# Rangefinders.net
KiCad netlist of a schematic drawn in Altium Designer
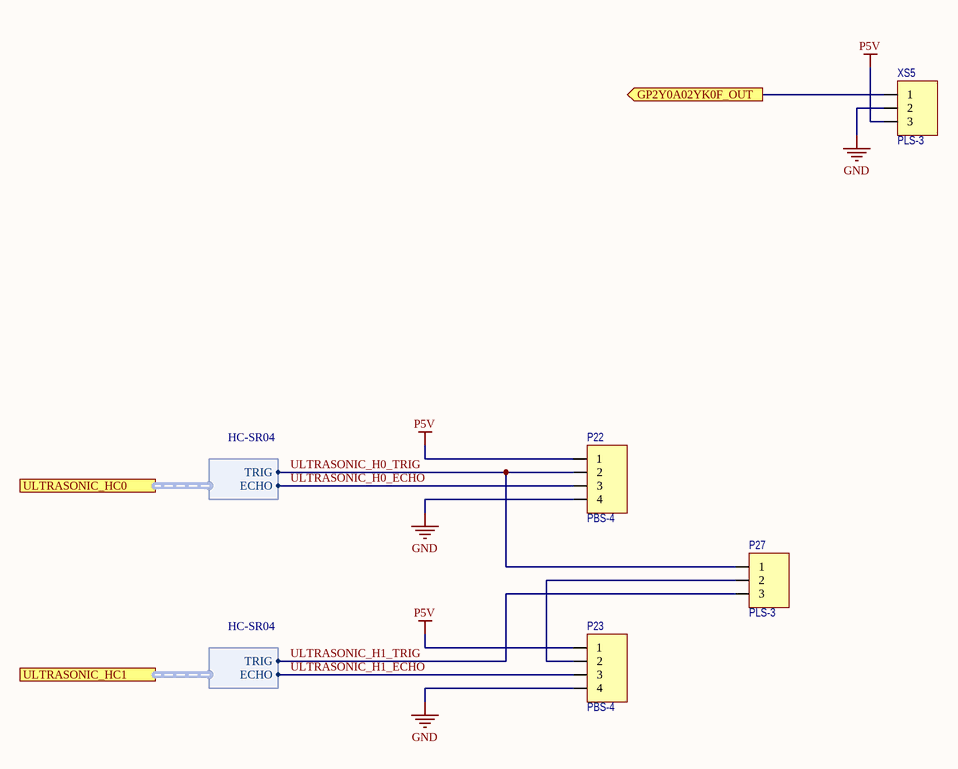
[diagram p0: Rangefinders.SchDoc]

(export (version "E")
  (design (tool "Eeschema 10.0.6"))
  (components
    (comp (ref "P22") (value "PBS-4") (footprint "PBS-4") (libsource (lib "my_AP_lib_sch") (part "PBS-4")))
    (comp (ref "P23") (value "PBS-4") (footprint "PBS-4") (libsource (lib "my_AP_lib_sch") (part "PBS-4")))
    (comp (ref "P27") (value "PLS-3") (footprint "PLS-3") (libsource (lib "my_AP_lib_sch") (part "PLS-3")))
    (comp (ref "XS5") (value "PLS-3") (footprint "PBS2-3") (libsource (lib "my_AP_lib_sch") (part "PBS2-3")))
  )
  (nets
    (net (code "2") (name "/GP2Y0A02YK0F_OUT") (class "Default")
      (node (ref "XS5") (pin "1") (pinfunction "1_1") (pintype "passive"))
    )
    (net (code "3") (name "/ULTRASONIC_H0_ECHO") (class "Default")
      (node (ref "P22") (pin "3") (pinfunction "3_3") (pintype "passive"))
    )
    (net (code "4") (name "/ULTRASONIC_H0_TRIG") (class "Default")
      (node (ref "P22") (pin "2") (pinfunction "2_2") (pintype "passive"))
      (node (ref "P27") (pin "1") (pinfunction "1_1") (pintype "passive"))
    )
    (net (code "5") (name "/ULTRASONIC_H1_ECHO") (class "Default")
      (node (ref "P23") (pin "3") (pinfunction "3_3") (pintype "passive"))
    )
    (net (code "6") (name "/ULTRASONIC_H1_TRIG") (class "Default")
      (node (ref "P27") (pin "3") (pinfunction "3_3") (pintype "passive"))
    )
    (net (code "8") (name "GND") (class "Default")
      (node (ref "P22") (pin "4") (pinfunction "4_4") (pintype "passive"))
      (node (ref "P23") (pin "4") (pinfunction "4_4") (pintype "passive"))
      (node (ref "XS5") (pin "2") (pinfunction "2_2") (pintype "passive"))
    )
    (net (code "9") (name "Net-(P23-Pad2)") (class "Default")
      (node (ref "P23") (pin "2") (pinfunction "2_2") (pintype "passive"))
      (node (ref "P27") (pin "2") (pinfunction "2_2") (pintype "passive"))
    )
    (net (code "10") (name "P5V") (class "Default")
      (node (ref "P22") (pin "1") (pinfunction "1_1") (pintype "passive"))
      (node (ref "P23") (pin "1") (pinfunction "1_1") (pintype "passive"))
      (node (ref "XS5") (pin "3") (pinfunction "3_3") (pintype "passive"))
    )
  )
)
